# DRONE_RPI_SHIELD.net
KiCad netlist of a schematic drawn in EasyEDA
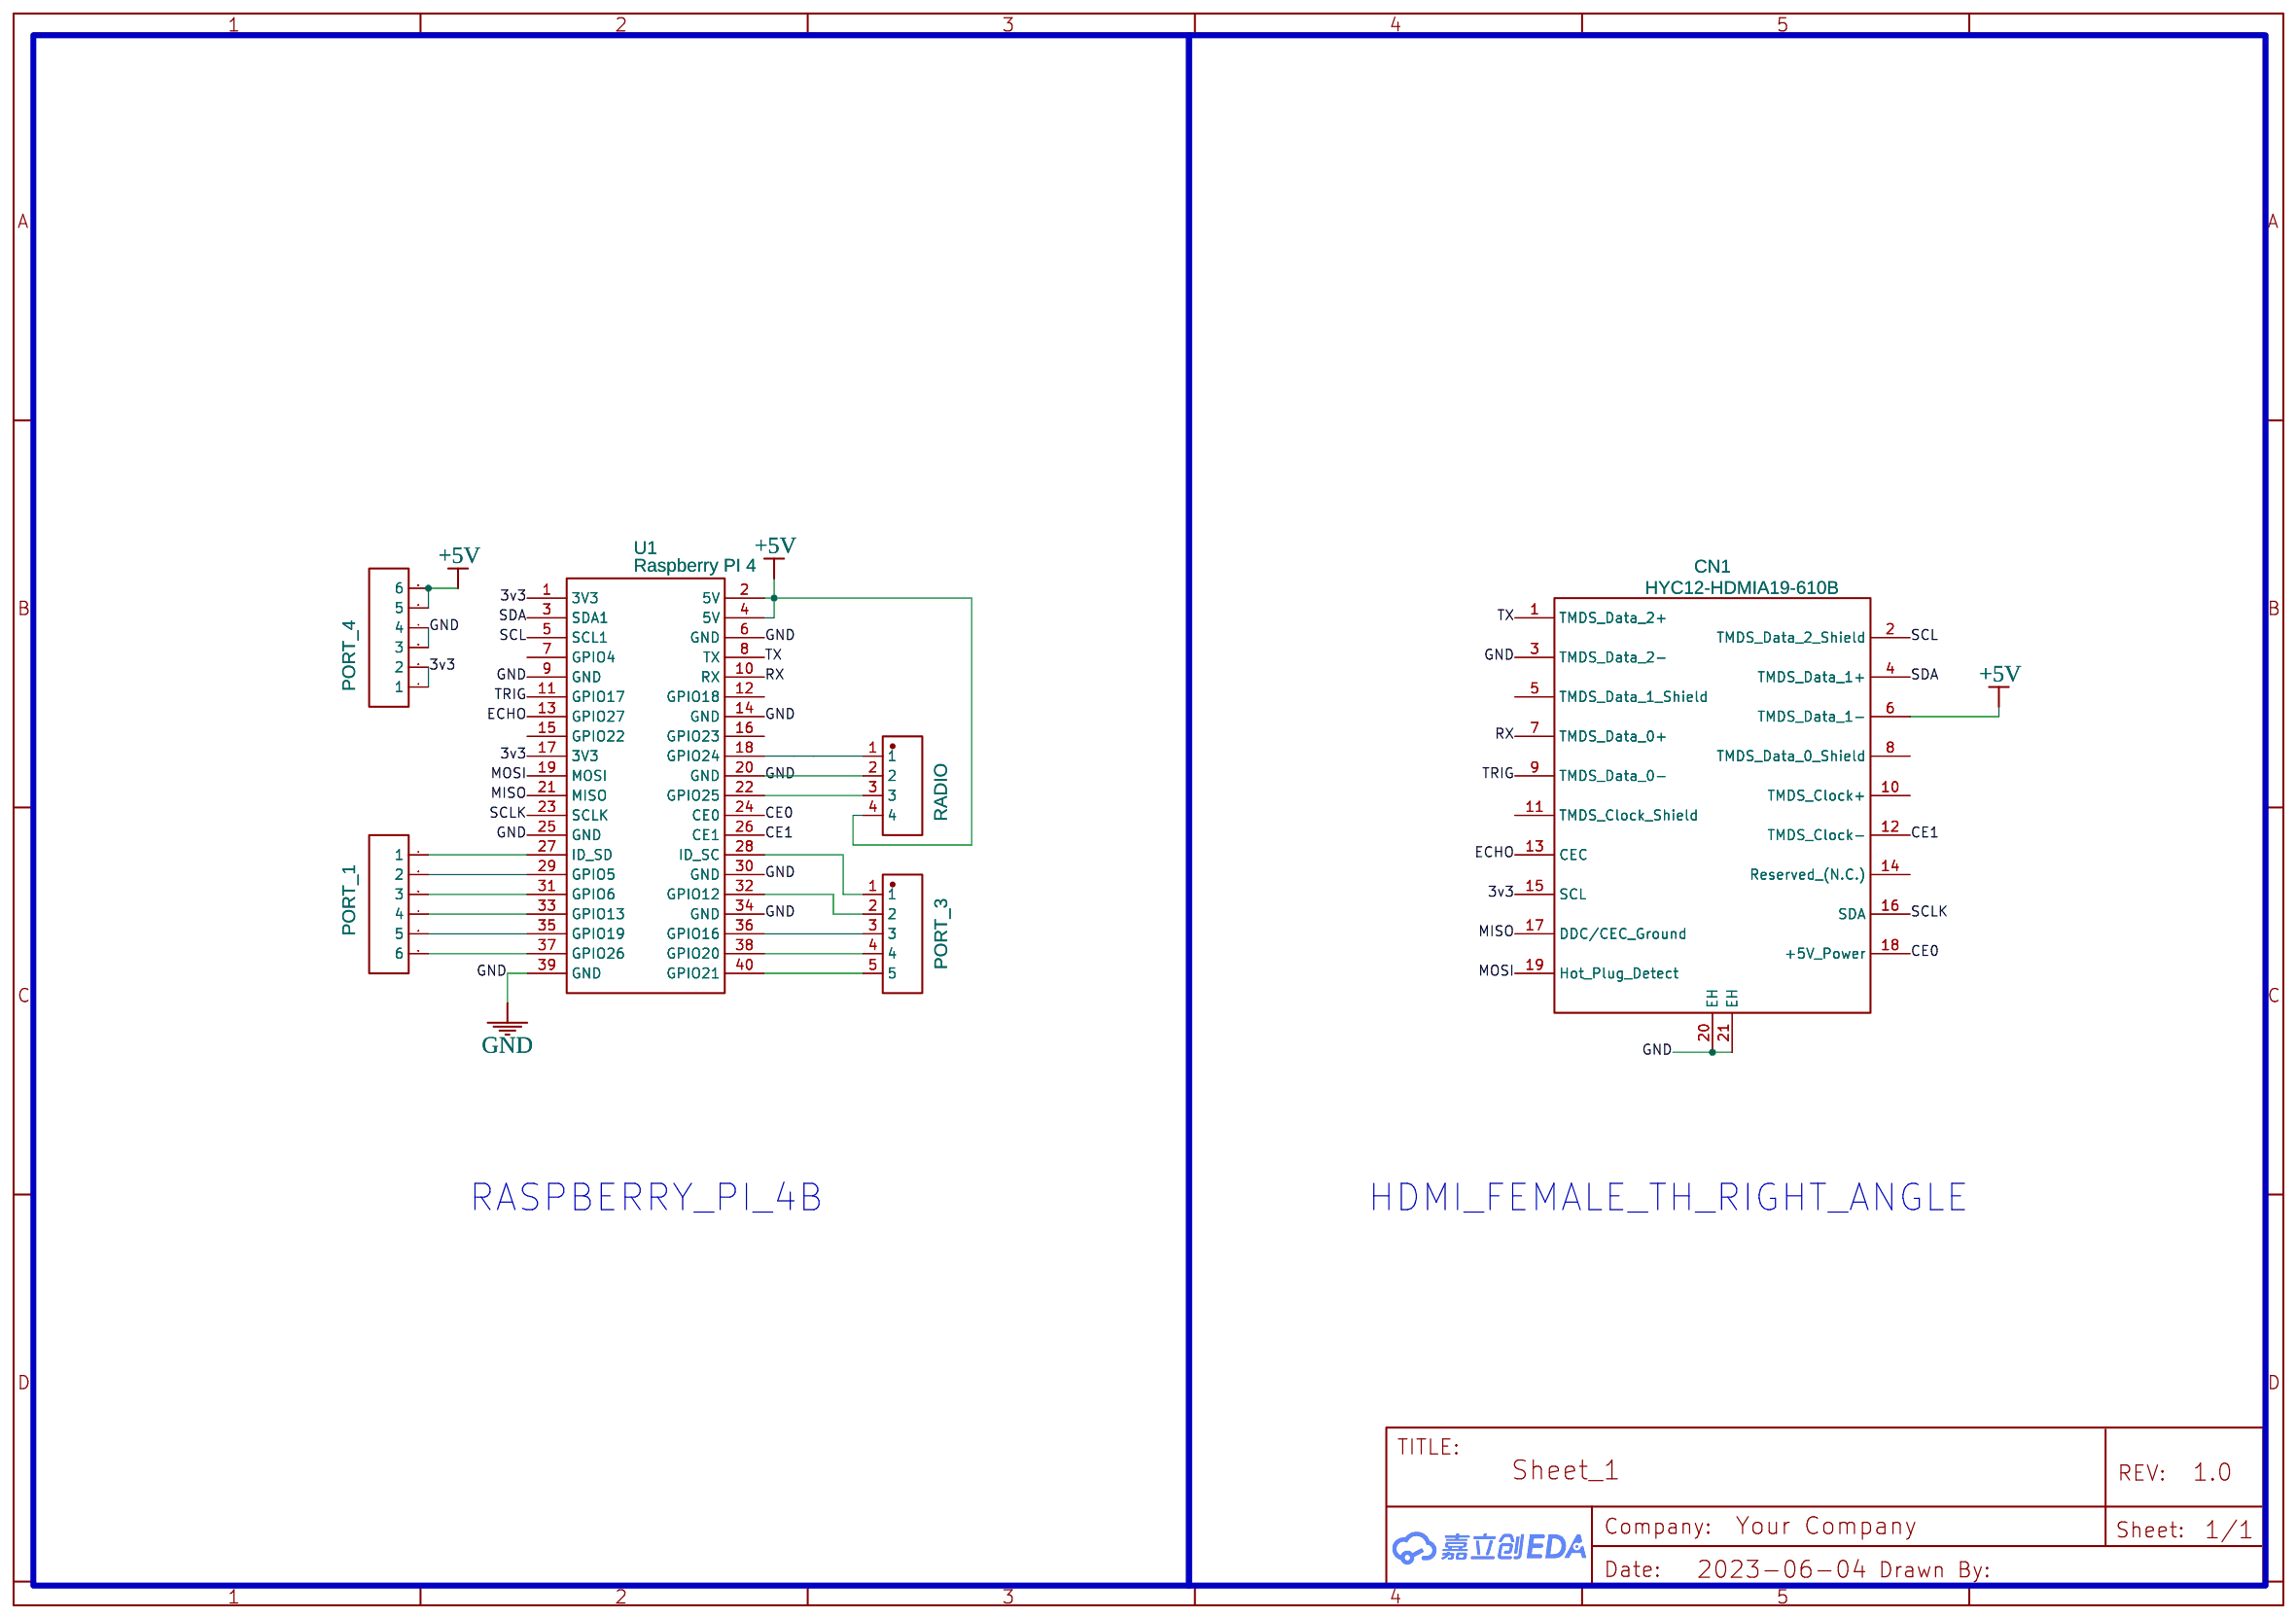
[diagram p0: schematic sheet]

(export (version "E")
  (design (tool "Eeschema 10.0.6"))
  (components
    (comp (ref "CN1")
      (value "HYC12-HDMIA19-610B")
      (fields (field (name "BOM_Supplier Part") "C711354"))
      (libsource (lib "") (part "HYC12-HDMIA19-610B"))
    )
    (comp (ref "PORT_1")
      (value "HEADER-MALE-2.54_1X6")
      (fields
        (field (name "BOM_Manufacturer Part") "Header-Male-2.54_1x6")
        (field (name "BOM_Supplier Part") "C37208")
      )
      (libsource (lib "") (part "HEADER-MALE-2.54_1X6"))
    )
    (comp (ref "PORT_3")
      (value "PZ254V-11-05P")
      (fields (field (name "BOM_Supplier Part") "C492404"))
      (libsource (lib "") (part "PZ254V-11-05P"))
    )
    (comp (ref "PORT_4")
      (value "HEADER-MALE-2.54_1X6")
      (fields
        (field (name "BOM_Manufacturer Part") "Header-Male-2.54_1x6")
        (field (name "BOM_Supplier Part") "C37208")
      )
      (libsource (lib "") (part "HEADER-MALE-2.54_1X6_1"))
    )
    (comp (ref "RADIO")
      (value "PZ254V-11-04P")
      (fields (field (name "BOM_Supplier Part") "C492403"))
      (libsource (lib "") (part "PZ254V-11-04P"))
    )
    (comp (ref "U1") (value "Raspberry PI 4") (libsource (lib "") (part "Raspberry PI 4")))
  )
  (nets
    (net (code "1") (name "+5V") (class "Default")
      (node (ref "CN1") (pin "6") (pinfunction "TMDS_Data_1-_6") (pintype "unspecified"))
      (node (ref "PORT_4") (pin "5") (pinfunction "5_5") (pintype "input"))
      (node (ref "PORT_4") (pin "6") (pinfunction "6_6") (pintype "input"))
      (node (ref "RADIO") (pin "4") (pinfunction "4_4") (pintype "unspecified"))
      (node (ref "U1") (pin "2") (pinfunction "5V_2") (pintype "unspecified"))
      (node (ref "U1") (pin "4") (pinfunction "5V_4") (pintype "unspecified"))
    )
    (net (code "2") (name "/3v3") (class "Default")
      (node (ref "CN1") (pin "15") (pinfunction "SCL_15") (pintype "unspecified"))
      (node (ref "PORT_4") (pin "1") (pinfunction "1_1") (pintype "input"))
      (node (ref "PORT_4") (pin "2") (pinfunction "2_2") (pintype "input"))
      (node (ref "U1") (pin "1") (pinfunction "3V3_1") (pintype "unspecified"))
      (node (ref "U1") (pin "17") (pinfunction "3V3_17") (pintype "unspecified"))
    )
    (net (code "3") (name "/CE0") (class "Default")
      (node (ref "CN1") (pin "18") (pinfunction "+5V_Power_18") (pintype "unspecified"))
      (node (ref "U1") (pin "24") (pinfunction "CE0_24") (pintype "unspecified"))
    )
    (net (code "4") (name "/CE1") (class "Default")
      (node (ref "CN1") (pin "12") (pinfunction "TMDS_Clock-_12") (pintype "unspecified"))
      (node (ref "U1") (pin "26") (pinfunction "CE1_26") (pintype "unspecified"))
    )
    (net (code "5") (name "/ECHO") (class "Default")
      (node (ref "CN1") (pin "13") (pinfunction "CEC_13") (pintype "unspecified"))
      (node (ref "U1") (pin "13") (pinfunction "GPIO27_13") (pintype "unspecified"))
    )
    (net (code "6") (name "/MISO") (class "Default")
      (node (ref "CN1") (pin "17") (pinfunction "DDC/CEC_Ground_17") (pintype "unspecified"))
      (node (ref "U1") (pin "21") (pinfunction "MISO_21") (pintype "unspecified"))
    )
    (net (code "7") (name "/MOSI") (class "Default")
      (node (ref "CN1") (pin "19") (pinfunction "Hot_Plug_Detect_19") (pintype "unspecified"))
      (node (ref "U1") (pin "19") (pinfunction "MOSI_19") (pintype "unspecified"))
    )
    (net (code "8") (name "/RX") (class "Default")
      (node (ref "CN1") (pin "7") (pinfunction "TMDS_Data_0+_7") (pintype "unspecified"))
      (node (ref "U1") (pin "10") (pinfunction "RX_10") (pintype "unspecified"))
    )
    (net (code "9") (name "/SCL") (class "Default")
      (node (ref "CN1") (pin "2") (pinfunction "TMDS_Data_2_Shield_2") (pintype "unspecified"))
      (node (ref "U1") (pin "5") (pinfunction "SCL1_5") (pintype "unspecified"))
    )
    (net (code "10") (name "/SCLK") (class "Default")
      (node (ref "CN1") (pin "16") (pinfunction "SDA_16") (pintype "unspecified"))
      (node (ref "U1") (pin "23") (pinfunction "SCLK_23") (pintype "unspecified"))
    )
    (net (code "11") (name "/SDA") (class "Default")
      (node (ref "CN1") (pin "4") (pinfunction "TMDS_Data_1+_4") (pintype "unspecified"))
      (node (ref "U1") (pin "3") (pinfunction "SDA1_3") (pintype "unspecified"))
    )
    (net (code "12") (name "/TRIG") (class "Default")
      (node (ref "CN1") (pin "9") (pinfunction "TMDS_Data_0-_9") (pintype "unspecified"))
      (node (ref "U1") (pin "11") (pinfunction "GPIO17_11") (pintype "unspecified"))
    )
    (net (code "13") (name "/TX") (class "Default")
      (node (ref "CN1") (pin "1") (pinfunction "TMDS_Data_2+_1") (pintype "unspecified"))
      (node (ref "U1") (pin "8") (pinfunction "TX_8") (pintype "unspecified"))
    )
    (net (code "14") (name "GND") (class "Default")
      (node (ref "CN1") (pin "20") (pinfunction "EH_20") (pintype "unspecified"))
      (node (ref "CN1") (pin "21") (pinfunction "EH_21") (pintype "unspecified"))
      (node (ref "CN1") (pin "3") (pinfunction "TMDS_Data_2-_3") (pintype "unspecified"))
      (node (ref "PORT_4") (pin "3") (pinfunction "3_3") (pintype "input"))
      (node (ref "PORT_4") (pin "4") (pinfunction "4_4") (pintype "input"))
      (node (ref "RADIO") (pin "2") (pinfunction "2_2") (pintype "unspecified"))
      (node (ref "U1") (pin "14") (pinfunction "GND_14") (pintype "unspecified"))
      (node (ref "U1") (pin "20") (pinfunction "GND_20") (pintype "unspecified"))
      (node (ref "U1") (pin "25") (pinfunction "GND_25") (pintype "unspecified"))
      (node (ref "U1") (pin "30") (pinfunction "GND_30") (pintype "unspecified"))
      (node (ref "U1") (pin "34") (pinfunction "GND_34") (pintype "unspecified"))
      (node (ref "U1") (pin "39") (pinfunction "GND_39") (pintype "unspecified"))
      (node (ref "U1") (pin "6") (pinfunction "GND_6") (pintype "unspecified"))
      (node (ref "U1") (pin "9") (pinfunction "GND_9") (pintype "unspecified"))
    )
    (net (code "15") (name "Net-(U1-GPIO5)") (class "Default")
      (node (ref "PORT_1") (pin "2") (pinfunction "2_2") (pintype "input"))
      (node (ref "U1") (pin "29") (pinfunction "GPIO5_29") (pintype "unspecified"))
    )
    (net (code "16") (name "Net-(U1-GPIO6)") (class "Default")
      (node (ref "PORT_1") (pin "3") (pinfunction "3_3") (pintype "input"))
      (node (ref "U1") (pin "31") (pinfunction "GPIO6_31") (pintype "unspecified"))
    )
    (net (code "17") (name "Net-(U1-GPIO12)") (class "Default")
      (node (ref "PORT_3") (pin "2") (pinfunction "2_2") (pintype "unspecified"))
      (node (ref "U1") (pin "32") (pinfunction "GPIO12_32") (pintype "unspecified"))
    )
    (net (code "18") (name "Net-(U1-GPIO13)") (class "Default")
      (node (ref "PORT_1") (pin "4") (pinfunction "4_4") (pintype "input"))
      (node (ref "U1") (pin "33") (pinfunction "GPIO13_33") (pintype "unspecified"))
    )
    (net (code "19") (name "Net-(U1-GPIO16)") (class "Default")
      (node (ref "PORT_3") (pin "3") (pinfunction "3_3") (pintype "unspecified"))
      (node (ref "U1") (pin "36") (pinfunction "GPIO16_36") (pintype "unspecified"))
    )
    (net (code "20") (name "Net-(U1-GPIO19)") (class "Default")
      (node (ref "PORT_1") (pin "5") (pinfunction "5_5") (pintype "input"))
      (node (ref "U1") (pin "35") (pinfunction "GPIO19_35") (pintype "unspecified"))
    )
    (net (code "21") (name "Net-(U1-GPIO20)") (class "Default")
      (node (ref "PORT_3") (pin "4") (pinfunction "4_4") (pintype "unspecified"))
      (node (ref "U1") (pin "38") (pinfunction "GPIO20_38") (pintype "unspecified"))
    )
    (net (code "22") (name "Net-(U1-GPIO21)") (class "Default")
      (node (ref "PORT_3") (pin "5") (pinfunction "5_5") (pintype "unspecified"))
      (node (ref "U1") (pin "40") (pinfunction "GPIO21_40") (pintype "unspecified"))
    )
    (net (code "23") (name "Net-(U1-GPIO24)") (class "Default")
      (node (ref "RADIO") (pin "1") (pinfunction "1_1") (pintype "unspecified"))
      (node (ref "U1") (pin "18") (pinfunction "GPIO24_18") (pintype "unspecified"))
    )
    (net (code "24") (name "Net-(U1-GPIO25)") (class "Default")
      (node (ref "RADIO") (pin "3") (pinfunction "3_3") (pintype "unspecified"))
      (node (ref "U1") (pin "22") (pinfunction "GPIO25_22") (pintype "unspecified"))
    )
    (net (code "25") (name "Net-(U1-GPIO26)") (class "Default")
      (node (ref "PORT_1") (pin "6") (pinfunction "6_6") (pintype "input"))
      (node (ref "U1") (pin "37") (pinfunction "GPIO26_37") (pintype "unspecified"))
    )
    (net (code "26") (name "Net-(U1-ID_SC)") (class "Default")
      (node (ref "PORT_3") (pin "1") (pinfunction "1_1") (pintype "unspecified"))
      (node (ref "U1") (pin "28") (pinfunction "ID_SC_28") (pintype "unspecified"))
    )
    (net (code "27") (name "Net-(U1-ID_SD)") (class "Default")
      (node (ref "PORT_1") (pin "1") (pinfunction "1_1") (pintype "input"))
      (node (ref "U1") (pin "27") (pinfunction "ID_SD_27") (pintype "unspecified"))
    )
    (net (code "28") (name "unconnected-(CN1-Reserved_(N.C.)-Pad14)") (class "Default")
      (node (ref "CN1") (pin "14") (pinfunction "Reserved_(N.C.)_14") (pintype "unspecified"))
    )
    (net (code "29") (name "unconnected-(CN1-TMDS_Clock+-Pad10)") (class "Default")
      (node (ref "CN1") (pin "10") (pinfunction "TMDS_Clock+_10") (pintype "unspecified"))
    )
    (net (code "30") (name "unconnected-(CN1-TMDS_Clock_Shield-Pad11)") (class "Default")
      (node (ref "CN1") (pin "11") (pinfunction "TMDS_Clock_Shield_11") (pintype "unspecified"))
    )
    (net (code "31") (name "unconnected-(CN1-TMDS_Data_0_Shield-Pad8)") (class "Default")
      (node (ref "CN1") (pin "8") (pinfunction "TMDS_Data_0_Shield_8") (pintype "unspecified"))
    )
    (net (code "32") (name "unconnected-(CN1-TMDS_Data_1_Shield-Pad5)") (class "Default")
      (node (ref "CN1") (pin "5") (pinfunction "TMDS_Data_1_Shield_5") (pintype "unspecified"))
    )
    (net (code "33") (name "unconnected-(U1-GPIO4-Pad7)") (class "Default")
      (node (ref "U1") (pin "7") (pinfunction "GPIO4_7") (pintype "unspecified"))
    )
    (net (code "34") (name "unconnected-(U1-GPIO18-Pad12)") (class "Default")
      (node (ref "U1") (pin "12") (pinfunction "GPIO18_12") (pintype "unspecified"))
    )
    (net (code "35") (name "unconnected-(U1-GPIO22-Pad15)") (class "Default")
      (node (ref "U1") (pin "15") (pinfunction "GPIO22_15") (pintype "unspecified"))
    )
    (net (code "36") (name "unconnected-(U1-GPIO23-Pad16)") (class "Default")
      (node (ref "U1") (pin "16") (pinfunction "GPIO23_16") (pintype "unspecified"))
    )
  )
)
